# SwitchEthernet_-_Rev_A6.net
KiCad netlist of a schematic drawn in EAGLE
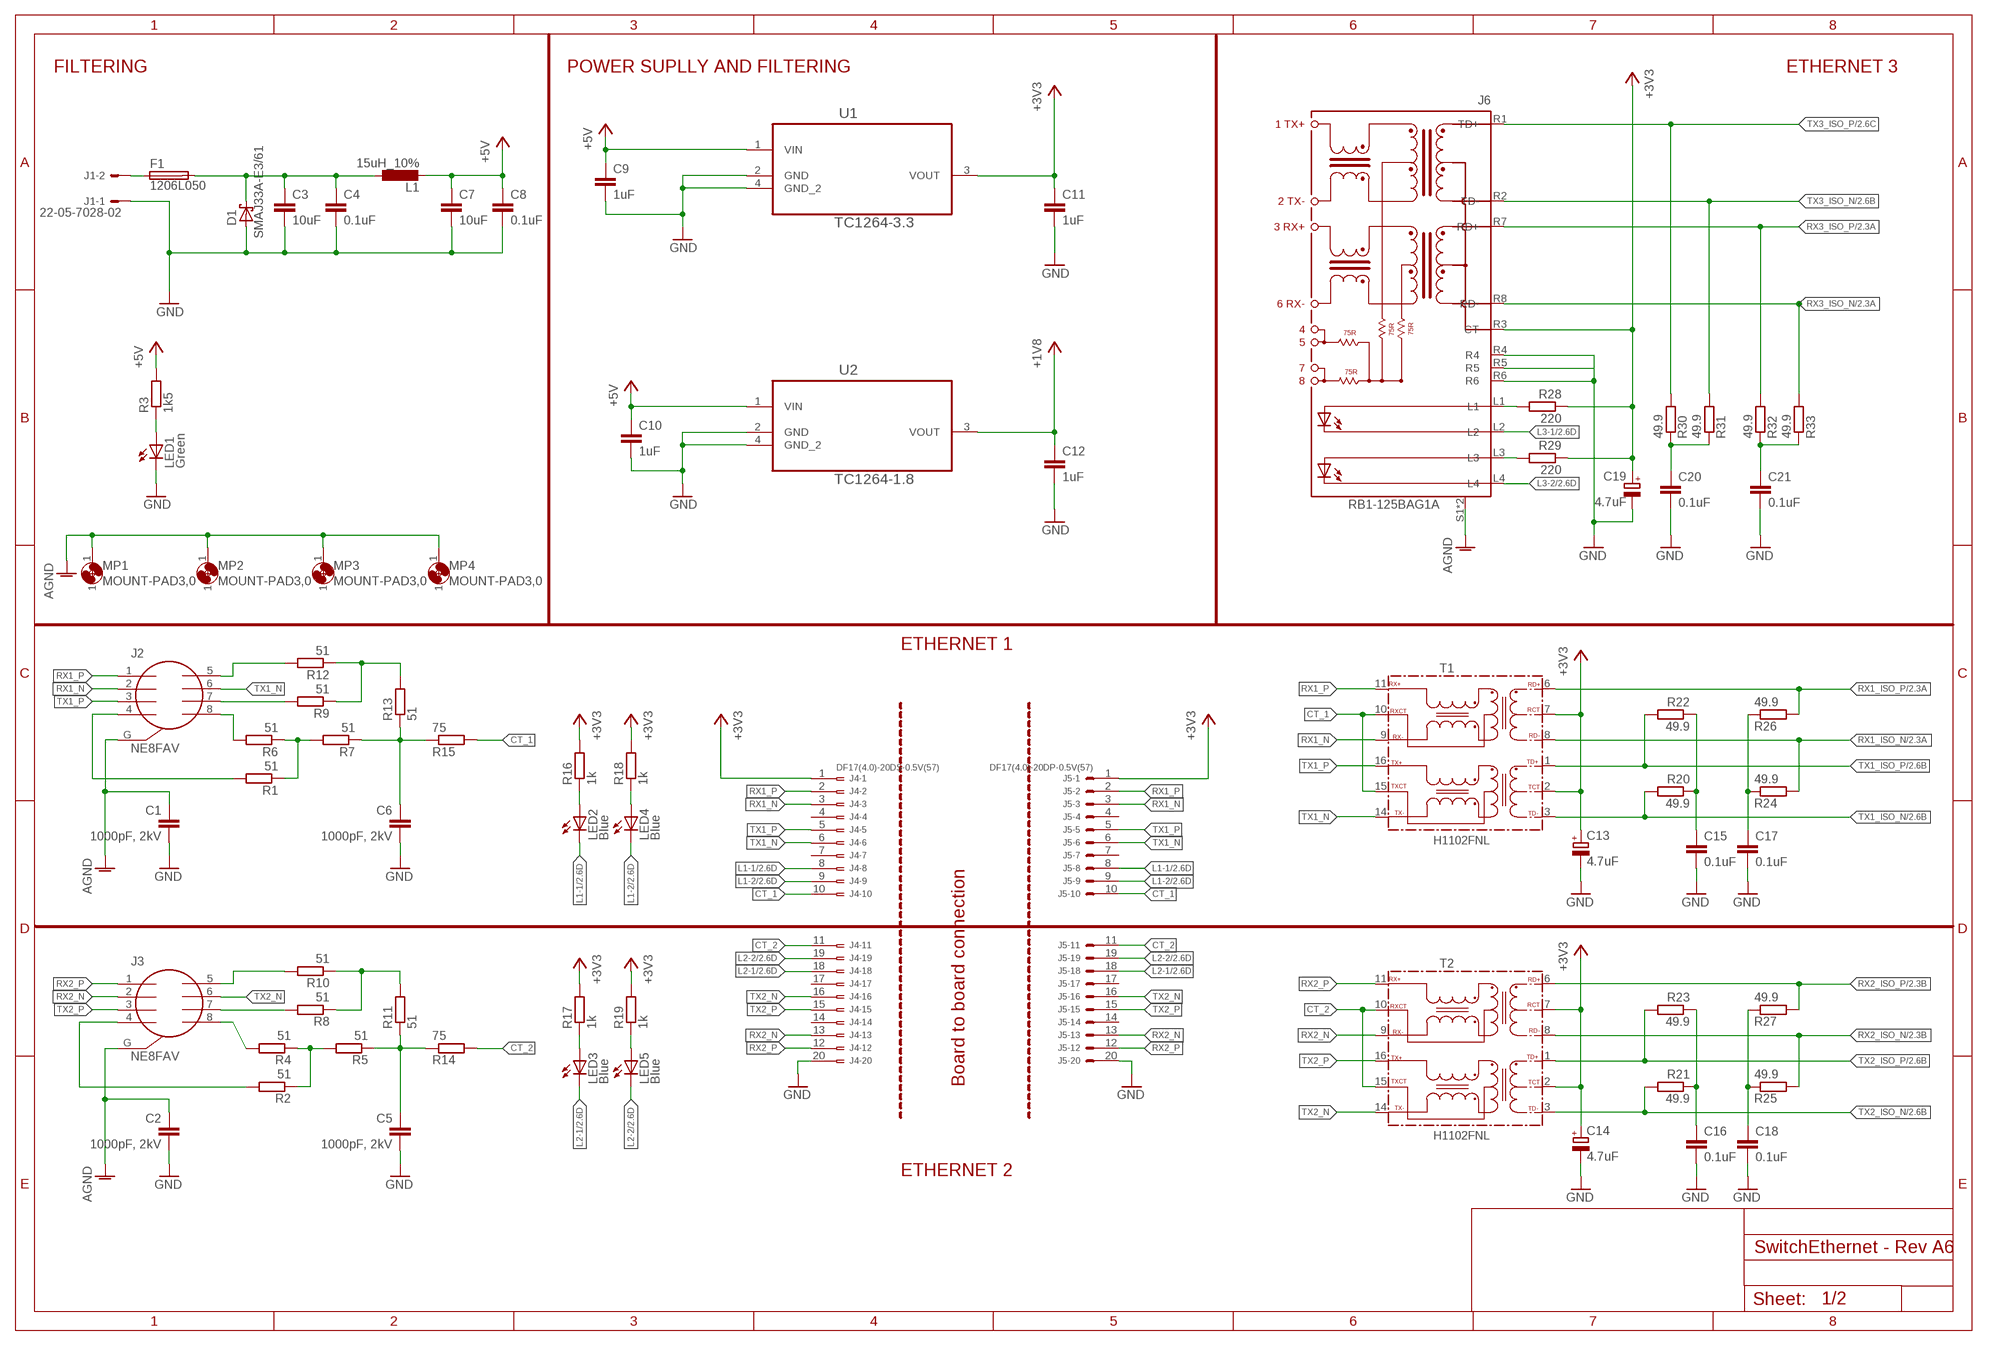
[diagram p0: schematic, sheet 1]
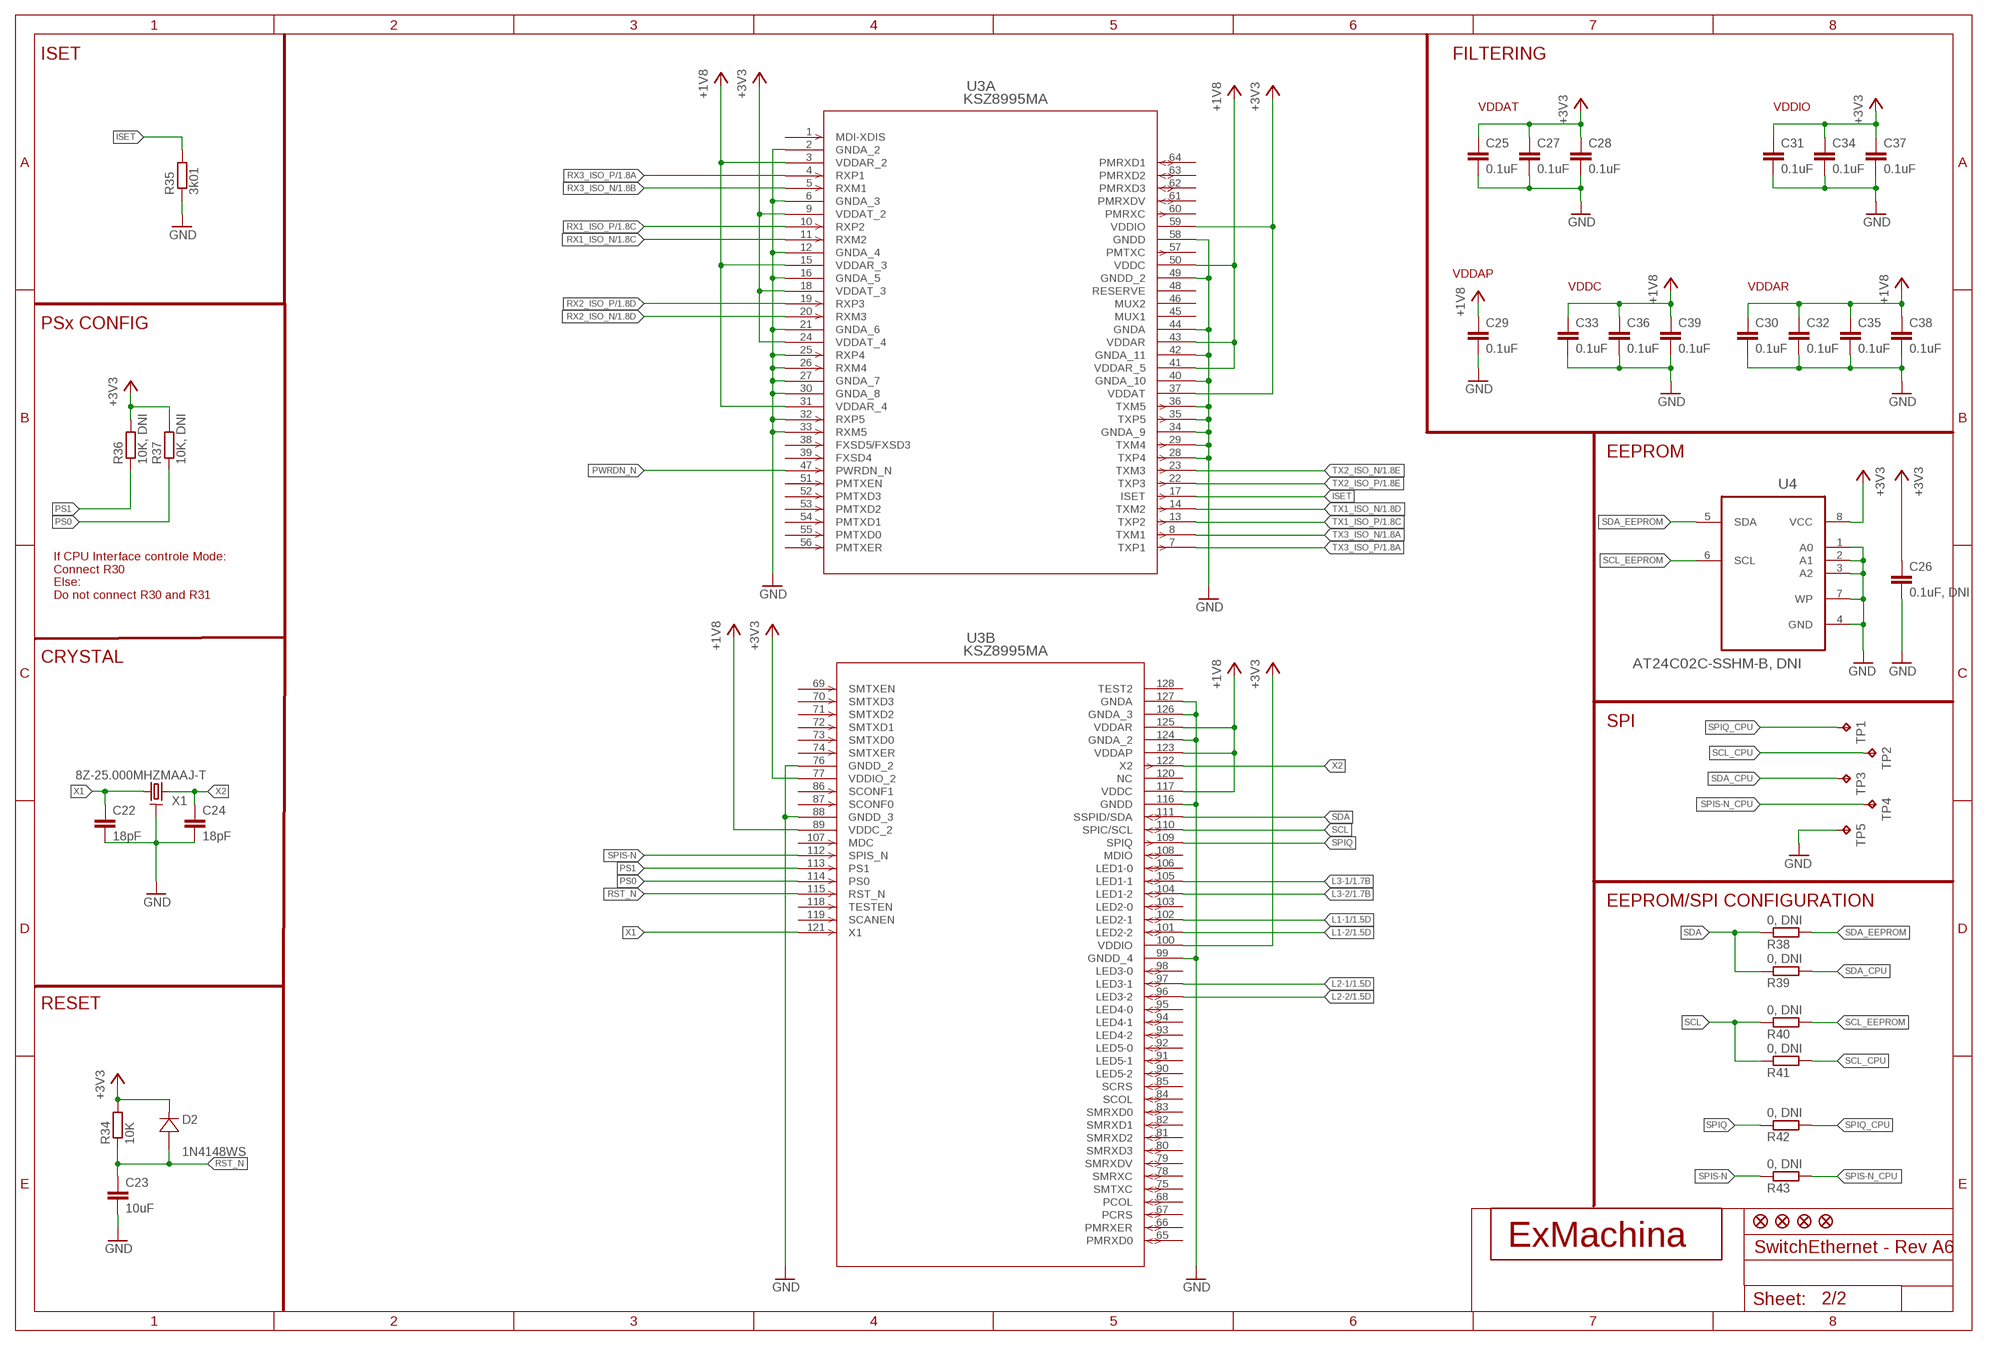
[diagram p1: schematic, sheet 2]

(export (version "E")
  (design (tool "Eeschema 10.0.6"))
  (components
    (comp (ref "C22")
      (value "18pF")
      (footprint "eagle-import:C0603")
      (fields (field (name "MF") "MURATA") (field (name "MPN") "GRM1885C1H180JA01D"))
      (libsource (lib "eagle-import") (part "C-EUC0603"))
    )
    (comp (ref "C23")
      (value "10uF")
      (footprint "eagle-import:C0603")
      (fields (field (name "MF") "MURATA") (field (name "MPN") "GRM32DR71C106KA01L"))
      (libsource (lib "eagle-import") (part "C-EUC0603"))
    )
    (comp (ref "C24")
      (value "18pF")
      (footprint "eagle-import:C0603")
      (fields (field (name "MF") "MURATA") (field (name "MPN") "GRM1885C1H180JA01D"))
      (libsource (lib "eagle-import") (part "C-EUC0603"))
    )
    (comp (ref "C25")
      (value "0.1uF")
      (footprint "eagle-import:C0603")
      (fields (field (name "MF") "MURATA") (field (name "MPN") "GRM188R71H104KA93D"))
      (libsource (lib "eagle-import") (part "C-EUC0603"))
    )
    (comp (ref "C26")
      (value "0.1uF, DNI")
      (footprint "eagle-import:C0603")
      (fields (field (name "MF") "MURATA") (field (name "MPN") "GRM188R71H104KA93D"))
      (libsource (lib "eagle-import") (part "C-EUC0603"))
    )
    (comp (ref "C27")
      (value "0.1uF")
      (footprint "eagle-import:C0603")
      (fields (field (name "MF") "MURATA") (field (name "MPN") "GRM188R71H104KA93D"))
      (libsource (lib "eagle-import") (part "C-EUC0603"))
    )
    (comp (ref "C28")
      (value "0.1uF")
      (footprint "eagle-import:C0603")
      (fields (field (name "MF") "MURATA") (field (name "MPN") "GRM188R71H104KA93D"))
      (libsource (lib "eagle-import") (part "C-EUC0603"))
    )
    (comp (ref "C29")
      (value "0.1uF")
      (footprint "eagle-import:C0603")
      (fields (field (name "MF") "MURATA") (field (name "MPN") "GRM188R71H104KA93D"))
      (libsource (lib "eagle-import") (part "C-EUC0603"))
    )
    (comp (ref "C30")
      (value "0.1uF")
      (footprint "eagle-import:C0603")
      (fields (field (name "MF") "MURATA") (field (name "MPN") "GRM188R71H104KA93D"))
      (libsource (lib "eagle-import") (part "C-EUC0603"))
    )
    (comp (ref "C31")
      (value "0.1uF")
      (footprint "eagle-import:C0603")
      (fields (field (name "MF") "MURATA") (field (name "MPN") "GRM188R71H104KA93D"))
      (libsource (lib "eagle-import") (part "C-EUC0603"))
    )
    (comp (ref "C32")
      (value "0.1uF")
      (footprint "eagle-import:C0603")
      (fields (field (name "MF") "MURATA") (field (name "MPN") "GRM188R71H104KA93D"))
      (libsource (lib "eagle-import") (part "C-EUC0603"))
    )
    (comp (ref "C33")
      (value "0.1uF")
      (footprint "eagle-import:C0603")
      (fields (field (name "MF") "MURATA") (field (name "MPN") "GRM188R71H104KA93D"))
      (libsource (lib "eagle-import") (part "C-EUC0603"))
    )
    (comp (ref "C34")
      (value "0.1uF")
      (footprint "eagle-import:C0603")
      (fields (field (name "MF") "MURATA") (field (name "MPN") "GRM188R71H104KA93D"))
      (libsource (lib "eagle-import") (part "C-EUC0603"))
    )
    (comp (ref "C35")
      (value "0.1uF")
      (footprint "eagle-import:C0603")
      (fields (field (name "MF") "MURATA") (field (name "MPN") "GRM188R71H104KA93D"))
      (libsource (lib "eagle-import") (part "C-EUC0603"))
    )
    (comp (ref "C36")
      (value "0.1uF")
      (footprint "eagle-import:C0603")
      (fields (field (name "MF") "MURATA") (field (name "MPN") "GRM188R71H104KA93D"))
      (libsource (lib "eagle-import") (part "C-EUC0603"))
    )
    (comp (ref "C37")
      (value "0.1uF")
      (footprint "eagle-import:C0603")
      (fields (field (name "MF") "MURATA") (field (name "MPN") "GRM188R71H104KA93D"))
      (libsource (lib "eagle-import") (part "C-EUC0603"))
    )
    (comp (ref "C38")
      (value "0.1uF")
      (footprint "eagle-import:C0603")
      (fields (field (name "MF") "MURATA") (field (name "MPN") "GRM188R71H104KA93D"))
      (libsource (lib "eagle-import") (part "C-EUC0603"))
    )
    (comp (ref "C39")
      (value "0.1uF")
      (footprint "eagle-import:C0603")
      (fields (field (name "MF") "MURATA") (field (name "MPN") "GRM188R71H104KA93D"))
      (libsource (lib "eagle-import") (part "C-EUC0603"))
    )
    (comp (ref "D2")
      (value "1N4148WS")
      (footprint "eagle-import:SOD323-W")
      (fields (field (name "MF") "ON SEMICONDUCTOR"))
      (libsource (lib "eagle-import") (part "1N4148WS"))
    )
    (comp (ref "JP1")
      (value "FIDUCIAL1X2")
      (footprint "eagle-import:FIDUCIAL-1X2")
      (libsource (lib "eagle-import") (part "FIDUCIAL1X2"))
    )
    (comp (ref "JP2")
      (value "FIDUCIAL1X2")
      (footprint "eagle-import:FIDUCIAL-1X2")
      (libsource (lib "eagle-import") (part "FIDUCIAL1X2"))
    )
    (comp (ref "JP3")
      (value "FIDUCIAL1X2")
      (footprint "eagle-import:FIDUCIAL-1X2")
      (libsource (lib "eagle-import") (part "FIDUCIAL1X2"))
    )
    (comp (ref "JP4")
      (value "FIDUCIAL1X2")
      (footprint "eagle-import:FIDUCIAL-1X2")
      (libsource (lib "eagle-import") (part "FIDUCIAL1X2"))
    )
    (comp (ref "R34")
      (value "10K")
      (footprint "eagle-import:R0603")
      (fields (field (name "MF") "YAGEO") (field (name "MPN") "RC0603FR-0710KL"))
      (libsource (lib "eagle-import") (part "R-EU_R0603"))
    )
    (comp (ref "R35")
      (value "3k01")
      (footprint "eagle-import:R0603")
      (fields (field (name "MF") "MULTICOMP") (field (name "MPN") "MCMR06X3001FTL"))
      (libsource (lib "eagle-import") (part "R-EU_R0603"))
    )
    (comp (ref "R36")
      (value "10K, DNI")
      (footprint "eagle-import:R0603")
      (fields (field (name "MF") "YAGEO") (field (name "MPN") "RC0603FR-0710KL"))
      (libsource (lib "eagle-import") (part "R-EU_R0603"))
    )
    (comp (ref "R37")
      (value "10K, DNI")
      (footprint "eagle-import:R0603")
      (fields (field (name "MF") "YAGEO") (field (name "MPN") "RC0603FR-0710KL"))
      (libsource (lib "eagle-import") (part "R-EU_R0603"))
    )
    (comp (ref "R38")
      (value "0, DNI")
      (footprint "eagle-import:R0603")
      (fields (field (name "MF") "YAGEO") (field (name "MPN") "RC0603FR-070RL"))
      (libsource (lib "eagle-import") (part "R-EU_R0603"))
    )
    (comp (ref "R39")
      (value "0, DNI")
      (footprint "eagle-import:R0603")
      (fields (field (name "MF") "YAGEO") (field (name "MPN") "RC0603FR-070RL"))
      (libsource (lib "eagle-import") (part "R-EU_R0603"))
    )
    (comp (ref "R40")
      (value "0, DNI")
      (footprint "eagle-import:R0603")
      (fields (field (name "MF") "YAGEO") (field (name "MPN") "RC0603FR-070RL"))
      (libsource (lib "eagle-import") (part "R-EU_R0603"))
    )
    (comp (ref "R41")
      (value "0, DNI")
      (footprint "eagle-import:R0603")
      (fields (field (name "MF") "YAGEO") (field (name "MPN") "RC0603FR-070RL"))
      (libsource (lib "eagle-import") (part "R-EU_R0603"))
    )
    (comp (ref "R42")
      (value "0, DNI")
      (footprint "eagle-import:R0603")
      (fields (field (name "MF") "YAGEO") (field (name "MPN") "RC0603FR-070RL"))
      (libsource (lib "eagle-import") (part "R-EU_R0603"))
    )
    (comp (ref "R43")
      (value "0, DNI")
      (footprint "eagle-import:R0603")
      (fields (field (name "MF") "YAGEO") (field (name "MPN") "RC0603FR-070RL"))
      (libsource (lib "eagle-import") (part "R-EU_R0603"))
    )
    (comp (ref "T3")
      (value "EXMACHINA-LOGO-NAME")
      (footprint "eagle-import:EXM-LOGO-BASELINE")
      (libsource (lib "eagle-import") (part "EXMACHINA-LOGO-NAME"))
    )
    (comp (ref "TP1")
      (value "TPB1,27")
      (footprint "eagle-import:B1,27")
      (libsource (lib "eagle-import") (part "TPB1,27"))
    )
    (comp (ref "TP2")
      (value "TPB1,27")
      (footprint "eagle-import:B1,27")
      (libsource (lib "eagle-import") (part "TPB1,27"))
    )
    (comp (ref "TP3")
      (value "TPB1,27")
      (footprint "eagle-import:B1,27")
      (libsource (lib "eagle-import") (part "TPB1,27"))
    )
    (comp (ref "TP4")
      (value "TPB1,27")
      (footprint "eagle-import:B1,27")
      (libsource (lib "eagle-import") (part "TPB1,27"))
    )
    (comp (ref "TP5")
      (value "TPB1,27")
      (footprint "eagle-import:B1,27")
      (libsource (lib "eagle-import") (part "TPB1,27"))
    )
    (comp (ref "U3")
      (value "KSZ8995MA")
      (footprint "eagle-import:PQFP-128_MQL")
      (fields
        (field (name "MF") "MICROCHIP")
        (field (name "MPN") "KSZ8995MA")
        (field (name "OC_FARNELL") "2509844")
        (field (name "OC_NEWARK") "unknown")
      )
      (libsource (lib "eagle-import") (part "KSZ8995MA"))
    )
    (comp (ref "U4")
      (value "AT24C02C-SSHM-B, DNI")
      (footprint "eagle-import:SOIC127P600X175-8N")
      (fields
        (field (name "MPN") "AT24C02C-SSHM-B")
        (field (name "MF") "MICROCHIP")
        (field (name "OC_FARNELL") "1971995")
      )
      (libsource (lib "eagle-import") (part "AT24C02C-SSHM-B"))
    )
    (comp (ref "X1")
      (value "8Z-25.000MHZMAAJ-T")
      (footprint "eagle-import:SMD2.5X2")
      (fields (field (name "MF") "TXC") (field (name "MPN") "8Z-25.000MAAJ-T"))
      (libsource (lib "eagle-import") (part "8Z-25.000MHZMAAJ-T"))
    )
    (comp (ref "C1")
      (value "1000pF, 2kV")
      (footprint "eagle-import:C1206")
      (fields (field (name "MF") "MULTICOMP") (field (name "MPN") "MC1206B102K202CT"))
      (libsource (lib "eagle-import") (part "C-EUC1206"))
    )
    (comp (ref "C2")
      (value "1000pF, 2kV")
      (footprint "eagle-import:C1206")
      (fields (field (name "MF") "MULTICOMP") (field (name "MPN") "MC1206B102K202CT"))
      (libsource (lib "eagle-import") (part "C-EUC1206"))
    )
    (comp (ref "C3")
      (value "10uF")
      (footprint "eagle-import:C0603")
      (fields (field (name "MF") "MURATA") (field (name "MPN") "GRM32DR71C106KA01L"))
      (libsource (lib "eagle-import") (part "C-EUC0603"))
    )
    (comp (ref "C4")
      (value "0.1uF")
      (footprint "eagle-import:C0603")
      (fields (field (name "MF") "MURATA") (field (name "MPN") "GRM188R71H104KA93D"))
      (libsource (lib "eagle-import") (part "C-EUC0603"))
    )
    (comp (ref "C5")
      (value "1000pF, 2kV")
      (footprint "eagle-import:C1206")
      (fields (field (name "MF") "MULTICOMP") (field (name "MPN") "MC1206B102K202CT"))
      (libsource (lib "eagle-import") (part "C-EUC1206"))
    )
    (comp (ref "C6")
      (value "1000pF, 2kV")
      (footprint "eagle-import:C1206")
      (fields (field (name "MF") "MULTICOMP") (field (name "MPN") "MC1206B102K202CT"))
      (libsource (lib "eagle-import") (part "C-EUC1206"))
    )
    (comp (ref "C7")
      (value "10uF")
      (footprint "eagle-import:C0603")
      (fields (field (name "MF") "MURATA") (field (name "MPN") "GRM32DR71C106KA01L"))
      (libsource (lib "eagle-import") (part "C-EUC0603"))
    )
    (comp (ref "C8")
      (value "0.1uF")
      (footprint "eagle-import:C0603")
      (fields (field (name "MF") "MURATA") (field (name "MPN") "GRM188R71H104KA93D"))
      (libsource (lib "eagle-import") (part "C-EUC0603"))
    )
    (comp (ref "C9")
      (value "1uF")
      (footprint "eagle-import:C0603")
      (fields (field (name "MF") "MURATA") (field (name "MPN") "GRM188R61C105KA93D"))
      (libsource (lib "eagle-import") (part "C-EUC0603"))
    )
    (comp (ref "C10")
      (value "1uF")
      (footprint "eagle-import:C0603")
      (fields (field (name "MF") "MURATA") (field (name "MPN") "GRM188R61C105KA93D"))
      (libsource (lib "eagle-import") (part "C-EUC0603"))
    )
    (comp (ref "C11")
      (value "1uF")
      (footprint "eagle-import:C0603")
      (fields (field (name "MF") "MURATA") (field (name "MPN") "GRM188R61C105KA93D"))
      (libsource (lib "eagle-import") (part "C-EUC0603"))
    )
    (comp (ref "C12")
      (value "1uF")
      (footprint "eagle-import:C0603")
      (fields (field (name "MF") "MURATA") (field (name "MPN") "GRM188R61C105KA93D"))
      (libsource (lib "eagle-import") (part "C-EUC0603"))
    )
    (comp (ref "C13")
      (value "4.7uF")
      (footprint "eagle-import:CT3216")
      (fields (field (name "MF") "KEMET") (field (name "MPN") "T491A475K016AT"))
      (libsource (lib "eagle-import") (part "CPOL-EUCT3216"))
    )
    (comp (ref "C14")
      (value "4.7uF")
      (footprint "eagle-import:CT3216")
      (fields (field (name "MF") "KEMET") (field (name "MPN") "T491A475K016AT"))
      (libsource (lib "eagle-import") (part "CPOL-EUCT3216"))
    )
    (comp (ref "C15")
      (value "0.1uF")
      (footprint "eagle-import:C0603")
      (fields (field (name "MF") "MURATA") (field (name "MPN") "GRM188R71H104KA93D"))
      (libsource (lib "eagle-import") (part "C-EUC0603"))
    )
    (comp (ref "C16")
      (value "0.1uF")
      (footprint "eagle-import:C0603")
      (fields (field (name "MF") "MURATA") (field (name "MPN") "GRM188R71H104KA93D"))
      (libsource (lib "eagle-import") (part "C-EUC0603"))
    )
    (comp (ref "C17")
      (value "0.1uF")
      (footprint "eagle-import:C0603")
      (fields (field (name "MF") "MURATA") (field (name "MPN") "GRM188R71H104KA93D"))
      (libsource (lib "eagle-import") (part "C-EUC0603"))
    )
    (comp (ref "C18")
      (value "0.1uF")
      (footprint "eagle-import:C0603")
      (fields (field (name "MF") "MURATA") (field (name "MPN") "GRM188R71H104KA93D"))
      (libsource (lib "eagle-import") (part "C-EUC0603"))
    )
    (comp (ref "C19")
      (value "4.7uF")
      (footprint "eagle-import:CT3216")
      (fields (field (name "MF") "KEMET") (field (name "MPN") "T491A475K016AT"))
      (libsource (lib "eagle-import") (part "CPOL-EUCT3216"))
    )
    (comp (ref "C20")
      (value "0.1uF")
      (footprint "eagle-import:C0603")
      (fields (field (name "MF") "MURATA") (field (name "MPN") "GRM188R71H104KA93D"))
      (libsource (lib "eagle-import") (part "C-EUC0603"))
    )
    (comp (ref "C21")
      (value "0.1uF")
      (footprint "eagle-import:C0603")
      (fields (field (name "MF") "MURATA") (field (name "MPN") "GRM188R71H104KA93D"))
      (libsource (lib "eagle-import") (part "C-EUC0603"))
    )
    (comp (ref "D1")
      (value "SMAJ33A-E3/61")
      (footprint "eagle-import:DIODE_DO-214AC")
      (fields (field (name "MF") "VISHAY"))
      (libsource (lib "eagle-import") (part "SMAJ33A-E3/61"))
    )
    (comp (ref "F1")
      (value "1206L050")
      (footprint "eagle-import:1206L")
      (fields (field (name "MF") "LITTELFUSE") (field (name "MPN") "1206L050YR"))
      (libsource (lib "eagle-import") (part "1206L050"))
    )
    (comp (ref "J1")
      (value "22-05-7028-02")
      (footprint "eagle-import:7395-02")
      (fields (field (name "MF") "MOLEX") (field (name "MPN") "22-05-7028"))
      (libsource (lib "eagle-import") (part "22-?-0205-7028"))
    )
    (comp (ref "J2")
      (value "NE8FAV")
      (footprint "eagle-import:NE8FAV")
      (fields (field (name "MF") "NEUTRIK") (field (name "OC_FARNELL") "1202031"))
      (libsource (lib "eagle-import") (part "NE8FAV"))
    )
    (comp (ref "J3")
      (value "NE8FAV")
      (footprint "eagle-import:NE8FAV")
      (fields (field (name "MF") "NEUTRIK") (field (name "OC_FARNELL") "1202031"))
      (libsource (lib "eagle-import") (part "NE8FAV"))
    )
    (comp (ref "J4")
      (value "DF17(4.0)-20DS-0.5V(57)")
      (footprint "eagle-import:DF17-20DS")
      (fields
        (field (name "MF") "HIROSE(HRS)")
        (field (name "MPN") "DF17(4.0)-20DS-0.5V(57)")
        (field (name "OC_FARNELL") "2300346")
        (field (name "OC_NEWARK") "unknown")
      )
      (libsource (lib "eagle-import") (part "DF17(?)-20DS-0.5V(57)4.0"))
    )
    (comp (ref "J5")
      (value "DF17(4.0)-20DP-0.5V(57)")
      (footprint "eagle-import:DF17-20DP")
      (fields
        (field (name "MF") "HIROSE(HRS)")
        (field (name "MPN") "DF17(4.0)-20DP-0.5V(57)")
        (field (name "OC_FARNELL") "2300344")
        (field (name "OC_NEWARK") "unknown")
      )
      (libsource (lib "eagle-import") (part "DF17(?)-20DP-0.5V(57)4.0"))
    )
    (comp (ref "J6")
      (value "RB1-125BAG1A")
      (footprint "eagle-import:WIZNET_RB1-125BAG1A")
      (libsource (lib "eagle-import") (part "RB1-125BAG1A"))
    )
    (comp (ref "L1")
      (value "15uH_10%")
      (footprint "eagle-import:L4532M")
      (fields (field (name "MF") "MURATA") (field (name "MPN") "LQH43CN150K03L"))
      (libsource (lib "eagle-import") (part "L-EUL4532C"))
    )
    (comp (ref "LED1")
      (value "Green")
      (footprint "eagle-import:CHIP-LED0603")
      (fields (field (name "MF") "MULTICOMP") (field (name "MPN") "OVS-0604"))
      (libsource (lib "eagle-import") (part "LEDCHIP-LED0603"))
    )
    (comp (ref "LED2")
      (value "Blue")
      (footprint "eagle-import:CHIP-LED0603")
      (fields (field (name "MF") "MULTICOMP") (field (name "MPN") "OVS-0603"))
      (libsource (lib "eagle-import") (part "LEDCHIP-LED0603"))
    )
    (comp (ref "LED3")
      (value "Blue")
      (footprint "eagle-import:CHIP-LED0603")
      (fields (field (name "MF") "MULTICOMP") (field (name "MPN") "OVS-0603"))
      (libsource (lib "eagle-import") (part "LEDCHIP-LED0603"))
    )
    (comp (ref "LED4")
      (value "Blue")
      (footprint "eagle-import:CHIP-LED0603")
      (fields (field (name "MF") "MULTICOMP") (field (name "MPN") "OVS-0603"))
      (libsource (lib "eagle-import") (part "LEDCHIP-LED0603"))
    )
    (comp (ref "LED5")
      (value "Blue")
      (footprint "eagle-import:CHIP-LED0603")
      (fields (field (name "MF") "MULTICOMP") (field (name "MPN") "OVS-0603"))
      (libsource (lib "eagle-import") (part "LEDCHIP-LED0603"))
    )
    (comp (ref "MP1")
      (value "MOUNT-PAD3,0")
      (footprint "eagle-import:P3,0")
      (libsource (lib "eagle-import") (part "MOUNT-PAD3,0"))
    )
    (comp (ref "MP2")
      (value "MOUNT-PAD3,0")
      (footprint "eagle-import:P3,0")
      (libsource (lib "eagle-import") (part "MOUNT-PAD3,0"))
    )
    (comp (ref "MP3")
      (value "MOUNT-PAD3,0")
      (footprint "eagle-import:P3,0")
      (libsource (lib "eagle-import") (part "MOUNT-PAD3,0"))
    )
    (comp (ref "MP4")
      (value "MOUNT-PAD3,0")
      (footprint "eagle-import:P3,0")
      (libsource (lib "eagle-import") (part "MOUNT-PAD3,0"))
    )
    (comp (ref "R1")
      (value "51")
      (footprint "eagle-import:R0603")
      (fields (field (name "MF") "YAGEO") (field (name "MPN") "RC0603FR-0751RL"))
      (libsource (lib "eagle-import") (part "R-EU_R0603"))
    )
    (comp (ref "R2")
      (value "51")
      (footprint "eagle-import:R0603")
      (fields (field (name "MF") "YAGEO") (field (name "MPN") "RC0603FR-0751RL"))
      (libsource (lib "eagle-import") (part "R-EU_R0603"))
    )
    (comp (ref "R3")
      (value "1k5")
      (footprint "eagle-import:R0603")
      (fields (field (name "MF") "YAGEO") (field (name "MPN") "RC0603FR-071K5L"))
      (libsource (lib "eagle-import") (part "R-EU_R0603"))
    )
    (comp (ref "R4")
      (value "51")
      (footprint "eagle-import:R0603")
      (fields (field (name "MF") "YAGEO") (field (name "MPN") "RC0603FR-0751RL"))
      (libsource (lib "eagle-import") (part "R-EU_R0603"))
    )
    (comp (ref "R5")
      (value "51")
      (footprint "eagle-import:R0603")
      (fields (field (name "MF") "YAGEO") (field (name "MPN") "RC0603FR-0751RL"))
      (libsource (lib "eagle-import") (part "R-EU_R0603"))
    )
    (comp (ref "R6")
      (value "51")
      (footprint "eagle-import:R0603")
      (fields (field (name "MF") "YAGEO") (field (name "MPN") "RC0603FR-0751RL"))
      (libsource (lib "eagle-import") (part "R-EU_R0603"))
    )
    (comp (ref "R7")
      (value "51")
      (footprint "eagle-import:R0603")
      (fields (field (name "MF") "YAGEO") (field (name "MPN") "RC0603FR-0751RL"))
      (libsource (lib "eagle-import") (part "R-EU_R0603"))
    )
    (comp (ref "R8")
      (value "51")
      (footprint "eagle-import:R0603")
      (fields (field (name "MF") "YAGEO") (field (name "MPN") "RC0603FR-0751RL"))
      (libsource (lib "eagle-import") (part "R-EU_R0603"))
    )
    (comp (ref "R9")
      (value "51")
      (footprint "eagle-import:R0603")
      (fields (field (name "MF") "YAGEO") (field (name "MPN") "RC0603FR-0751RL"))
      (libsource (lib "eagle-import") (part "R-EU_R0603"))
    )
    (comp (ref "R10")
      (value "51")
      (footprint "eagle-import:R0603")
      (fields (field (name "MF") "YAGEO") (field (name "MPN") "RC0603FR-0751RL"))
      (libsource (lib "eagle-import") (part "R-EU_R0603"))
    )
    (comp (ref "R11")
      (value "51")
      (footprint "eagle-import:R0603")
      (fields (field (name "MF") "YAGEO") (field (name "MPN") "RC0603FR-0751RL"))
      (libsource (lib "eagle-import") (part "R-EU_R0603"))
    )
    (comp (ref "R12")
      (value "51")
      (footprint "eagle-import:R0603")
      (fields (field (name "MF") "YAGEO") (field (name "MPN") "RC0603FR-0751RL"))
      (libsource (lib "eagle-import") (part "R-EU_R0603"))
    )
    (comp (ref "R13")
      (value "51")
      (footprint "eagle-import:R0603")
      (fields (field (name "MF") "YAGEO") (field (name "MPN") "RC0603FR-0751RL"))
      (libsource (lib "eagle-import") (part "R-EU_R0603"))
    )
    (comp (ref "R14")
      (value "75")
      (footprint "eagle-import:R0603")
      (fields (field (name "MF") "YAGEO") (field (name "MPN") "RC0603FR-0775RL"))
      (libsource (lib "eagle-import") (part "R-EU_R0603"))
    )
    (comp (ref "R15")
      (value "75")
      (footprint "eagle-import:R0603")
      (fields (field (name "MF") "YAGEO") (field (name "MPN") "RC0603FR-0775RL"))
      (libsource (lib "eagle-import") (part "R-EU_R0603"))
    )
    (comp (ref "R16")
      (value "1k")
      (footprint "eagle-import:R0603")
      (fields (field (name "MF") "YAGEO") (field (name "MPN") "RC0603FR-071KL."))
      (libsource (lib "eagle-import") (part "R-EU_R0603"))
    )
    (comp (ref "R17")
      (value "1k")
      (footprint "eagle-import:R0603")
      (fields (field (name "MF") "YAGEO") (field (name "MPN") "RC0603FR-071KL."))
      (libsource (lib "eagle-import") (part "R-EU_R0603"))
    )
    (comp (ref "R18")
      (value "1k")
      (footprint "eagle-import:R0603")
      (fields (field (name "MF") "YAGEO") (field (name "MPN") "RC0603FR-071KL."))
      (libsource (lib "eagle-import") (part "R-EU_R0603"))
    )
    (comp (ref "R19")
      (value "1k")
      (footprint "eagle-import:R0603")
      (fields (field (name "MF") "YAGEO") (field (name "MPN") "RC0603FR-071KL."))
      (libsource (lib "eagle-import") (part "R-EU_R0603"))
    )
    (comp (ref "R20")
      (value "49.9")
      (footprint "eagle-import:R0603")
      (fields (field (name "MF") "MULTICOMP") (field (name "MPN") "MCWR06X49R9FTL"))
      (libsource (lib "eagle-import") (part "R-EU_R0603"))
    )
    (comp (ref "R21")
      (value "49.9")
      (footprint "eagle-import:R0603")
      (fields (field (name "MF") "MULTICOMP") (field (name "MPN") "MCWR06X49R9FTL"))
      (libsource (lib "eagle-import") (part "R-EU_R0603"))
    )
    (comp (ref "R22")
      (value "49.9")
      (footprint "eagle-import:R0603")
      (fields (field (name "MF") "MULTICOMP") (field (name "MPN") "MCWR06X49R9FTL"))
      (libsource (lib "eagle-import") (part "R-EU_R0603"))
    )
    (comp (ref "R23")
      (value "49.9")
      (footprint "eagle-import:R0603")
      (fields (field (name "MF") "MULTICOMP") (field (name "MPN") "MCWR06X49R9FTL"))
      (libsource (lib "eagle-import") (part "R-EU_R0603"))
    )
    (comp (ref "R24")
      (value "49.9")
      (footprint "eagle-import:R0603")
      (fields (field (name "MF") "MULTICOMP") (field (name "MPN") "MCWR06X49R9FTL"))
      (libsource (lib "eagle-import") (part "R-EU_R0603"))
    )
    (comp (ref "R25")
      (value "49.9")
      (footprint "eagle-import:R0603")
      (fields (field (name "MF") "MULTICOMP") (field (name "MPN") "MCWR06X49R9FTL"))
      (libsource (lib "eagle-import") (part "R-EU_R0603"))
    )
    (comp (ref "R26")
      (value "49.9")
      (footprint "eagle-import:R0603")
      (fields (field (name "MF") "MULTICOMP") (field (name "MPN") "MCWR06X49R9FTL"))
      (libsource (lib "eagle-import") (part "R-EU_R0603"))
    )
    (comp (ref "R27")
      (value "49.9")
      (footprint "eagle-import:R0603")
      (fields (field (name "MF") "MULTICOMP") (field (name "MPN") "MCWR06X49R9FTL"))
      (libsource (lib "eagle-import") (part "R-EU_R0603"))
    )
    (comp (ref "R28")
      (value "220")
      (footprint "eagle-import:R0603")
      (fields (field (name "MF") "YAGEO (PHYCOMP)") (field (name "MPN") "RC0603FR-07220RL"))
      (libsource (lib "eagle-import") (part "R-EU_R0603"))
    )
    (comp (ref "R29")
      (value "220")
      (footprint "eagle-import:R0603")
      (fields (field (name "MF") "YAGEO (PHYCOMP)") (field (name "MPN") "RC0603FR-07220RL"))
      (libsource (lib "eagle-import") (part "R-EU_R0603"))
    )
    (comp (ref "R30")
      (value "49.9")
      (footprint "eagle-import:R0603")
      (fields (field (name "MF") "MULTICOMP") (field (name "MPN") "MCWR06X49R9FTL"))
      (libsource (lib "eagle-import") (part "R-EU_R0603"))
    )
    (comp (ref "R31")
      (value "49.9")
      (footprint "eagle-import:R0603")
      (fields (field (name "MF") "MULTICOMP") (field (name "MPN") "MCWR06X49R9FTL"))
      (libsource (lib "eagle-import") (part "R-EU_R0603"))
    )
    (comp (ref "R32")
      (value "49.9")
      (footprint "eagle-import:R0603")
      (fields (field (name "MF") "MULTICOMP") (field (name "MPN") "MCWR06X49R9FTL"))
      (libsource (lib "eagle-import") (part "R-EU_R0603"))
    )
    (comp (ref "R33")
      (value "49.9")
      (footprint "eagle-import:R0603")
      (fields (field (name "MF") "MULTICOMP") (field (name "MPN") "MCWR06X49R9FTL"))
      (libsource (lib "eagle-import") (part "R-EU_R0603"))
    )
    (comp (ref "T1")
      (value "H1102FNL")
      (footprint "eagle-import:HXXXX")
      (libsource (lib "eagle-import") (part "H1102FNL"))
    )
    (comp (ref "T2")
      (value "H1102FNL")
      (footprint "eagle-import:HXXXX")
      (libsource (lib "eagle-import") (part "H1102FNL"))
    )
    (comp (ref "U1")
      (value "TC1264-3.3")
      (footprint "eagle-import:SOT230P700X180-4N")
      (libsource (lib "eagle-import") (part "TC1264-3.3"))
    )
    (comp (ref "U2")
      (value "TC1264-1.8")
      (footprint "eagle-import:SOT230P700X180-4N")
      (libsource (lib "eagle-import") (part "TC1264-1.8"))
    )
  )
  (nets
    (net (code "1") (name "+1V8") (class "Default")
      (node (ref "C12") (pin "1") (pinfunction "1_1") (pintype "passive"))
      (node (ref "C29") (pin "1") (pinfunction "1_1") (pintype "passive"))
      (node (ref "C30") (pin "1") (pinfunction "1_1") (pintype "passive"))
      (node (ref "C32") (pin "1") (pinfunction "1_1") (pintype "passive"))
      (node (ref "C33") (pin "1") (pinfunction "1_1") (pintype "passive"))
      (node (ref "C35") (pin "1") (pinfunction "1_1") (pintype "passive"))
      (node (ref "C36") (pin "1") (pinfunction "1_1") (pintype "passive"))
      (node (ref "C38") (pin "1") (pinfunction "1_1") (pintype "passive"))
      (node (ref "C39") (pin "1") (pinfunction "1_1") (pintype "passive"))
      (node (ref "U2") (pin "3") (pinfunction "VOUT_3") (pintype "output"))
      (node (ref "U3") (pin "117") (pinfunction "VDDC_117") (pintype "power_in"))
      (node (ref "U3") (pin "123") (pinfunction "VDDAP_123") (pintype "power_in"))
      (node (ref "U3") (pin "125") (pinfunction "VDDAR_125") (pintype "power_in"))
      (node (ref "U3") (pin "15") (pinfunction "VDDAR_3_15") (pintype "power_in"))
      (node (ref "U3") (pin "3") (pinfunction "VDDAR_2_3") (pintype "power_in"))
      (node (ref "U3") (pin "31") (pinfunction "VDDAR_4_31") (pintype "power_in"))
      (node (ref "U3") (pin "41") (pinfunction "VDDAR_5_41") (pintype "power_in"))
      (node (ref "U3") (pin "43") (pinfunction "VDDAR_43") (pintype "power_in"))
      (node (ref "U3") (pin "50") (pinfunction "VDDC_50") (pintype "power_in"))
      (node (ref "U3") (pin "89") (pinfunction "VDDC_2_89") (pintype "power_in"))
    )
    (net (code "2") (name "+3V3") (class "Default")
      (node (ref "C11") (pin "1") (pinfunction "1_1") (pintype "passive"))
      (node (ref "C13") (pin "+") (pinfunction "+_+") (pintype "passive"))
      (node (ref "C14") (pin "+") (pinfunction "+_+") (pintype "passive"))
      (node (ref "C19") (pin "+") (pinfunction "+_+") (pintype "passive"))
      (node (ref "C25") (pin "1") (pinfunction "1_1") (pintype "passive"))
      (node (ref "C26") (pin "1") (pinfunction "1_1") (pintype "passive"))
      (node (ref "C27") (pin "1") (pinfunction "1_1") (pintype "passive"))
      (node (ref "C28") (pin "1") (pinfunction "1_1") (pintype "passive"))
      (node (ref "C31") (pin "1") (pinfunction "1_1") (pintype "passive"))
      (node (ref "C34") (pin "1") (pinfunction "1_1") (pintype "passive"))
      (node (ref "C37") (pin "1") (pinfunction "1_1") (pintype "passive"))
      (node (ref "D2") (pin "C") (pinfunction "1_C") (pintype "passive"))
      (node (ref "J4") (pin "1") (pinfunction "P_1") (pintype "bidirectional"))
      (node (ref "J5") (pin "1") (pinfunction "P_1") (pintype "bidirectional"))
      (node (ref "J6") (pin "R3") (pinfunction "CT_R3") (pintype "input"))
      (node (ref "R16") (pin "2") (pinfunction "2_2") (pintype "passive"))
      (node (ref "R17") (pin "2") (pinfunction "2_2") (pintype "passive"))
      (node (ref "R18") (pin "2") (pinfunction "2_2") (pintype "passive"))
      (node (ref "R19") (pin "2") (pinfunction "2_2") (pintype "passive"))
      (node (ref "R28") (pin "1") (pinfunction "1_1") (pintype "passive"))
      (node (ref "R29") (pin "1") (pinfunction "1_1") (pintype "passive"))
      (node (ref "R34") (pin "2") (pinfunction "2_2") (pintype "passive"))
      (node (ref "R36") (pin "2") (pinfunction "2_2") (pintype "passive"))
      (node (ref "R37") (pin "2") (pinfunction "2_2") (pintype "passive"))
      (node (ref "T1") (pin "2") (pinfunction "TCT_2") (pintype "bidirectional"))
      (node (ref "T1") (pin "7") (pinfunction "RCT_7") (pintype "bidirectional"))
      (node (ref "T2") (pin "2") (pinfunction "TCT_2") (pintype "bidirectional"))
      (node (ref "T2") (pin "7") (pinfunction "RCT_7") (pintype "bidirectional"))
      (node (ref "U1") (pin "3") (pinfunction "VOUT_3") (pintype "output"))
      (node (ref "U3") (pin "100") (pinfunction "VDDIO_100") (pintype "power_in"))
      (node (ref "U3") (pin "18") (pinfunction "VDDAT_3_18") (pintype "power_in"))
      (node (ref "U3") (pin "24") (pinfunction "VDDAT_4_24") (pintype "power_in"))
      (node (ref "U3") (pin "37") (pinfunction "VDDAT_37") (pintype "power_in"))
      (node (ref "U3") (pin "59") (pinfunction "VDDIO_59") (pintype "power_in"))
      (node (ref "U3") (pin "77") (pinfunction "VDDIO_2_77") (pintype "power_in"))
      (node (ref "U3") (pin "9") (pinfunction "VDDAT_2_9") (pintype "power_in"))
      (node (ref "U4") (pin "8") (pinfunction "VCC_8") (pintype "power_in"))
    )
    (net (code "3") (name "+5V") (class "Default")
      (node (ref "C10") (pin "1") (pinfunction "1_1") (pintype "passive"))
      (node (ref "C7") (pin "1") (pinfunction "1_1") (pintype "passive"))
      (node (ref "C8") (pin "1") (pinfunction "1_1") (pintype "passive"))
      (node (ref "C9") (pin "1") (pinfunction "1_1") (pintype "passive"))
      (node (ref "L1") (pin "2") (pinfunction "2_2") (pintype "passive"))
      (node (ref "R3") (pin "2") (pinfunction "2_2") (pintype "passive"))
      (node (ref "U1") (pin "1") (pinfunction "VIN_1") (pintype "input"))
      (node (ref "U2") (pin "1") (pinfunction "VIN_1") (pintype "input"))
    )
    (net (code "4") (name "AGND") (class "Default")
      (node (ref "C1") (pin "1") (pinfunction "1_1") (pintype "passive"))
      (node (ref "C2") (pin "1") (pinfunction "1_1") (pintype "passive"))
      (node (ref "J2") (pin "G") (pinfunction "G_G") (pintype "passive"))
      (node (ref "J3") (pin "G") (pinfunction "G_G") (pintype "passive"))
      (node (ref "J6") (pin "S1") (pinfunction "P$1_S1") (pintype "bidirectional"))
      (node (ref "J6") (pin "S2") (pinfunction "P$1_S2") (pintype "bidirectional"))
      (node (ref "MP1") (pin "1") (pinfunction "1_1") (pintype "power_in"))
      (node (ref "MP2") (pin "1") (pinfunction "1_1") (pintype "power_in"))
      (node (ref "MP3") (pin "1") (pinfunction "1_1") (pintype "power_in"))
      (node (ref "MP4") (pin "1") (pinfunction "1_1") (pintype "power_in"))
    )
    (net (code "5") (name "CT_1") (class "Default")
      (node (ref "J4") (pin "10") (pinfunction "P_10") (pintype "bidirectional"))
      (node (ref "J5") (pin "10") (pinfunction "P_10") (pintype "bidirectional"))
      (node (ref "R15") (pin "2") (pinfunction "2_2") (pintype "passive"))
      (node (ref "T1") (pin "10") (pinfunction "RXCT_10") (pintype "bidirectional"))
      (node (ref "T1") (pin "15") (pinfunction "TXCT_15") (pintype "bidirectional"))
    )
    (net (code "6") (name "CT_2") (class "Default")
      (node (ref "J4") (pin "11") (pinfunction "P_11") (pintype "bidirectional"))
      (node (ref "J5") (pin "11") (pinfunction "P_11") (pintype "bidirectional"))
      (node (ref "R14") (pin "2") (pinfunction "2_2") (pintype "passive"))
      (node (ref "T2") (pin "10") (pinfunction "RXCT_10") (pintype "bidirectional"))
      (node (ref "T2") (pin "15") (pinfunction "TXCT_15") (pintype "bidirectional"))
    )
    (net (code "7") (name "GND") (class "Default")
      (node (ref "C1") (pin "2") (pinfunction "2_2") (pintype "passive"))
      (node (ref "C10") (pin "2") (pinfunction "2_2") (pintype "passive"))
      (node (ref "C11") (pin "2") (pinfunction "2_2") (pintype "passive"))
      (node (ref "C12") (pin "2") (pinfunction "2_2") (pintype "passive"))
      (node (ref "C13") (pin "-") (pinfunction "-_-") (pintype "passive"))
      (node (ref "C14") (pin "-") (pinfunction "-_-") (pintype "passive"))
      (node (ref "C15") (pin "2") (pinfunction "2_2") (pintype "passive"))
      (node (ref "C16") (pin "2") (pinfunction "2_2") (pintype "passive"))
      (node (ref "C17") (pin "2") (pinfunction "2_2") (pintype "passive"))
      (node (ref "C18") (pin "2") (pinfunction "2_2") (pintype "passive"))
      (node (ref "C19") (pin "-") (pinfunction "-_-") (pintype "passive"))
      (node (ref "C2") (pin "2") (pinfunction "2_2") (pintype "passive"))
      (node (ref "C20") (pin "2") (pinfunction "2_2") (pintype "passive"))
      (node (ref "C21") (pin "2") (pinfunction "2_2") (pintype "passive"))
      (node (ref "C22") (pin "2") (pinfunction "2_2") (pintype "passive"))
      (node (ref "C23") (pin "2") (pinfunction "2_2") (pintype "passive"))
      (node (ref "C24") (pin "2") (pinfunction "2_2") (pintype "passive"))
      (node (ref "C25") (pin "2") (pinfunction "2_2") (pintype "passive"))
      (node (ref "C26") (pin "2") (pinfunction "2_2") (pintype "passive"))
      (node (ref "C27") (pin "2") (pinfunction "2_2") (pintype "passive"))
      (node (ref "C28") (pin "2") (pinfunction "2_2") (pintype "passive"))
      (node (ref "C29") (pin "2") (pinfunction "2_2") (pintype "passive"))
      (node (ref "C3") (pin "2") (pinfunction "2_2") (pintype "passive"))
      (node (ref "C30") (pin "2") (pinfunction "2_2") (pintype "passive"))
      (node (ref "C31") (pin "2") (pinfunction "2_2") (pintype "passive"))
      (node (ref "C32") (pin "2") (pinfunction "2_2") (pintype "passive"))
      (node (ref "C33") (pin "2") (pinfunction "2_2") (pintype "passive"))
      (node (ref "C34") (pin "2") (pinfunction "2_2") (pintype "passive"))
      (node (ref "C35") (pin "2") (pinfunction "2_2") (pintype "passive"))
      (node (ref "C36") (pin "2") (pinfunction "2_2") (pintype "passive"))
      (node (ref "C37") (pin "2") (pinfunction "2_2") (pintype "passive"))
      (node (ref "C38") (pin "2") (pinfunction "2_2") (pintype "passive"))
      (node (ref "C39") (pin "2") (pinfunction "2_2") (pintype "passive"))
      (node (ref "C4") (pin "2") (pinfunction "2_2") (pintype "passive"))
      (node (ref "C5") (pin "2") (pinfunction "2_2") (pintype "passive"))
      (node (ref "C6") (pin "2") (pinfunction "2_2") (pintype "passive"))
      (node (ref "C7") (pin "2") (pinfunction "2_2") (pintype "passive"))
      (node (ref "C8") (pin "2") (pinfunction "2_2") (pintype "passive"))
      (node (ref "C9") (pin "2") (pinfunction "2_2") (pintype "passive"))
      (node (ref "D1") (pin "2") (pinfunction "A_2") (pintype "passive"))
      (node (ref "J1") (pin "1") (pinfunction "S_1") (pintype "passive"))
      (node (ref "J4") (pin "20") (pinfunction "P_20") (pintype "bidirectional"))
      (node (ref "J5") (pin "20") (pinfunction "P_20") (pintype "bidirectional"))
      (node (ref "J6") (pin "R4") (pinfunction "R4_R4") (pintype "input"))
      (node (ref "J6") (pin "R5") (pinfunction "R5_R5") (pintype "input"))
      (node (ref "J6") (pin "R6") (pinfunction "R6_R6") (pintype "input"))
      (node (ref "LED1") (pin "C") (pinfunction "C_C") (pintype "passive"))
      (node (ref "R35") (pin "1") (pinfunction "1_1") (pintype "passive"))
      (node (ref "TP5") (pin "TP") (pinfunction "TP_TP") (pintype "input"))
      (node (ref "U1") (pin "2") (pinfunction "GND_2") (pintype "passive"))
      (node (ref "U1") (pin "4") (pinfunction "GND_2_4") (pintype "passive"))
      (node (ref "U2") (pin "2") (pinfunction "GND_2") (pintype "passive"))
      (node (ref "U2") (pin "4") (pinfunction "GND_2_4") (pintype "passive"))
      (node (ref "U3") (pin "116") (pinfunction "GNDD_116") (pintype "power_in"))
      (node (ref "U3") (pin "12") (pinfunction "GNDA_4_12") (pintype "power_in"))
      (node (ref "U3") (pin "124") (pinfunction "GNDA_2_124") (pintype "power_in"))
      (node (ref "U3") (pin "126") (pinfunction "GNDA_3_126") (pintype "power_in"))
      (node (ref "U3") (pin "127") (pinfunction "GNDA_127") (pintype "power_in"))
      (node (ref "U3") (pin "16") (pinfunction "GNDA_5_16") (pintype "power_in"))
      (node (ref "U3") (pin "2") (pinfunction "GNDA_2_2") (pintype "power_in"))
      (node (ref "U3") (pin "21") (pinfunction "GNDA_6_21") (pintype "power_in"))
      (node (ref "U3") (pin "25") (pinfunction "RXP4_25") (pintype "input"))
      (node (ref "U3") (pin "26") (pinfunction "RXM4_26") (pintype "input"))
      (node (ref "U3") (pin "27") (pinfunction "GNDA_7_27") (pintype "power_in"))
      (node (ref "U3") (pin "28") (pinfunction "TXP4_28") (pintype "output"))
      (node (ref "U3") (pin "29") (pinfunction "TXM4_29") (pintype "output"))
      (node (ref "U3") (pin "30") (pinfunction "GNDA_8_30") (pintype "power_in"))
      (node (ref "U3") (pin "32") (pinfunction "RXP5_32") (pintype "input"))
      (node (ref "U3") (pin "33") (pinfunction "RXM5_33") (pintype "input"))
      (node (ref "U3") (pin "34") (pinfunction "GNDA_9_34") (pintype "power_in"))
      (node (ref "U3") (pin "35") (pinfunction "TXP5_35") (pintype "output"))
      (node (ref "U3") (pin "36") (pinfunction "TXM5_36") (pintype "output"))
      (node (ref "U3") (pin "40") (pinfunction "GNDA_10_40") (pintype "power_in"))
      (node (ref "U3") (pin "42") (pinfunction "GNDA_11_42") (pintype "power_in"))
      (node (ref "U3") (pin "44") (pinfunction "GNDA_44") (pintype "power_in"))
      (node (ref "U3") (pin "49") (pinfunction "GNDD_2_49") (pintype "passive"))
      (node (ref "U3") (pin "58") (pinfunction "GNDD_58") (pintype "power_in"))
      (node (ref "U3") (pin "6") (pinfunction "GNDA_3_6") (pintype "power_in"))
      (node (ref "U3") (pin "76") (pinfunction "GNDD_2_76") (pintype "power_in"))
      (node (ref "U3") (pin "88") (pinfunction "GNDD_3_88") (pintype "power_in"))
      (node (ref "U3") (pin "99") (pinfunction "GNDD_4_99") (pintype "power_in"))
      (node (ref "U4") (pin "1") (pinfunction "A0_1") (pintype "input"))
      (node (ref "U4") (pin "2") (pinfunction "A1_2") (pintype "input"))
      (node (ref "U4") (pin "3") (pinfunction "A2_3") (pintype "input"))
      (node (ref "U4") (pin "4") (pinfunction "GND_4") (pintype "power_in"))
      (node (ref "U4") (pin "7") (pinfunction "WP_7") (pintype "input"))
      (node (ref "X1") (pin "2") (pinfunction "2_2") (pintype "passive"))
      (node (ref "X1") (pin "4") (pinfunction "2_4") (pintype "passive"))
    )
    (net (code "8") (name "ISET") (class "Default")
      (node (ref "R35") (pin "2") (pinfunction "2_2") (pintype "passive"))
      (node (ref "U3") (pin "17") (pinfunction "ISET_17") (pintype "output"))
    )
    (net (code "9") (name "L1-1") (class "Default")
      (node (ref "J4") (pin "8") (pinfunction "P_8") (pintype "bidirectional"))
      (node (ref "J5") (pin "8") (pinfunction "P_8") (pintype "bidirectional"))
      (node (ref "LED2") (pin "C") (pinfunction "C_C") (pintype "passive"))
      (node (ref "U3") (pin "102") (pinfunction "LED2-1_102") (pintype "bidirectional"))
    )
    (net (code "10") (name "L1-2") (class "Default")
      (node (ref "J4") (pin "9") (pinfunction "P_9") (pintype "bidirectional"))
      (node (ref "J5") (pin "9") (pinfunction "P_9") (pintype "bidirectional"))
      (node (ref "LED4") (pin "C") (pinfunction "C_C") (pintype "passive"))
      (node (ref "U3") (pin "101") (pinfunction "LED2-2_101") (pintype "bidirectional"))
    )
    (net (code "11") (name "L2-1") (class "Default")
      (node (ref "J4") (pin "18") (pinfunction "P_18") (pintype "bidirectional"))
      (node (ref "J5") (pin "18") (pinfunction "P_18") (pintype "bidirectional"))
      (node (ref "LED3") (pin "C") (pinfunction "C_C") (pintype "passive"))
      (node (ref "U3") (pin "97") (pinfunction "LED3-1_97") (pintype "bidirectional"))
    )
    (net (code "12") (name "L2-2") (class "Default")
      (node (ref "J4") (pin "19") (pinfunction "P_19") (pintype "bidirectional"))
      (node (ref "J5") (pin "19") (pinfunction "P_19") (pintype "bidirectional"))
      (node (ref "LED5") (pin "C") (pinfunction "C_C") (pintype "passive"))
      (node (ref "U3") (pin "96") (pinfunction "LED3-2_96") (pintype "bidirectional"))
    )
    (net (code "13") (name "L3-1") (class "Default")
      (node (ref "J6") (pin "L2") (pinfunction "L2_L2") (pintype "passive"))
      (node (ref "U3") (pin "105") (pinfunction "LED1-1_105") (pintype "bidirectional"))
    )
    (net (code "14") (name "L3-2") (class "Default")
      (node (ref "J6") (pin "L4") (pinfunction "L4_L4") (pintype "passive"))
      (node (ref "U3") (pin "104") (pinfunction "LED1-2_104") (pintype "bidirectional"))
    )
    (net (code "15") (name "Net-(C5-Pad1)") (class "Default")
      (node (ref "C5") (pin "1") (pinfunction "1_1") (pintype "passive"))
      (node (ref "R11") (pin "1") (pinfunction "1_1") (pintype "passive"))
      (node (ref "R14") (pin "1") (pinfunction "1_1") (pintype "passive"))
      (node (ref "R5") (pin "1") (pinfunction "1_1") (pintype "passive"))
    )
    (net (code "16") (name "Net-(C6-Pad1)") (class "Default")
      (node (ref "C6") (pin "1") (pinfunction "1_1") (pintype "passive"))
      (node (ref "R13") (pin "1") (pinfunction "1_1") (pintype "passive"))
      (node (ref "R15") (pin "1") (pinfunction "1_1") (pintype "passive"))
      (node (ref "R7") (pin "1") (pinfunction "1_1") (pintype "passive"))
    )
    (net (code "17") (name "Net-(C15-Pad1)") (class "Default")
      (node (ref "C15") (pin "1") (pinfunction "1_1") (pintype "passive"))
      (node (ref "R20") (pin "1") (pinfunction "1_1") (pintype "passive"))
      (node (ref "R22") (pin "1") (pinfunction "1_1") (pintype "passive"))
    )
    (net (code "18") (name "Net-(C16-Pad1)") (class "Default")
      (node (ref "C16") (pin "1") (pinfunction "1_1") (pintype "passive"))
      (node (ref "R21") (pin "1") (pinfunction "1_1") (pintype "passive"))
      (node (ref "R23") (pin "1") (pinfunction "1_1") (pintype "passive"))
    )
    (net (code "19") (name "Net-(C17-Pad1)") (class "Default")
      (node (ref "C17") (pin "1") (pinfunction "1_1") (pintype "passive"))
      (node (ref "R24") (pin "1") (pinfunction "1_1") (pintype "passive"))
      (node (ref "R26") (pin "1") (pinfunction "1_1") (pintype "passive"))
    )
    (net (code "20") (name "Net-(C18-Pad1)") (class "Default")
      (node (ref "C18") (pin "1") (pinfunction "1_1") (pintype "passive"))
      (node (ref "R25") (pin "1") (pinfunction "1_1") (pintype "passive"))
      (node (ref "R27") (pin "1") (pinfunction "1_1") (pintype "passive"))
    )
    (net (code "21") (name "Net-(C20-Pad1)") (class "Default")
      (node (ref "C20") (pin "1") (pinfunction "1_1") (pintype "passive"))
      (node (ref "R30") (pin "1") (pinfunction "1_1") (pintype "passive"))
      (node (ref "R31") (pin "1") (pinfunction "1_1") (pintype "passive"))
    )
    (net (code "22") (name "Net-(C21-Pad1)") (class "Default")
      (node (ref "C21") (pin "1") (pinfunction "1_1") (pintype "passive"))
      (node (ref "R32") (pin "1") (pinfunction "1_1") (pintype "passive"))
      (node (ref "R33") (pin "1") (pinfunction "1_1") (pintype "passive"))
    )
    (net (code "23") (name "Net-(D1-C)") (class "Default")
      (node (ref "C3") (pin "1") (pinfunction "1_1") (pintype "passive"))
      (node (ref "C4") (pin "1") (pinfunction "1_1") (pintype "passive"))
      (node (ref "D1") (pin "1") (pinfunction "C_1") (pintype "passive"))
      (node (ref "F1") (pin "2") (pinfunction "2_2") (pintype "passive"))
      (node (ref "L1") (pin "1") (pinfunction "1_1") (pintype "passive"))
    )
    (net (code "24") (name "Net-(J1B-S)") (class "Default")
      (node (ref "F1") (pin "1") (pinfunction "1_1") (pintype "passive"))
      (node (ref "J1") (pin "2") (pinfunction "S_2") (pintype "passive"))
    )
    (net (code "25") (name "Net-(J2-Pad4)") (class "Default")
      (node (ref "J2") (pin "4") (pinfunction "4_4") (pintype "passive"))
      (node (ref "R1") (pin "2") (pinfunction "2_2") (pintype "passive"))
    )
    (net (code "26") (name "Net-(J2-Pad5)") (class "Default")
      (node (ref "J2") (pin "5") (pinfunction "5_5") (pintype "passive"))
      (node (ref "R12") (pin "2") (pinfunction "2_2") (pintype "passive"))
    )
    (net (code "27") (name "Net-(J2-Pad7)") (class "Default")
      (node (ref "J2") (pin "7") (pinfunction "7_7") (pintype "passive"))
      (node (ref "R9") (pin "2") (pinfunction "2_2") (pintype "passive"))
    )
    (net (code "28") (name "Net-(J2-Pad8)") (class "Default")
      (node (ref "J2") (pin "8") (pinfunction "8_8") (pintype "passive"))
      (node (ref "R6") (pin "2") (pinfunction "2_2") (pintype "passive"))
    )
    (net (code "29") (name "Net-(J3-Pad4)") (class "Default")
      (node (ref "J3") (pin "4") (pinfunction "4_4") (pintype "passive"))
      (node (ref "R2") (pin "2") (pinfunction "2_2") (pintype "passive"))
    )
    (net (code "30") (name "Net-(J3-Pad5)") (class "Default")
      (node (ref "J3") (pin "5") (pinfunction "5_5") (pintype "passive"))
      (node (ref "R10") (pin "2") (pinfunction "2_2") (pintype "passive"))
    )
    (net (code "31") (name "Net-(J3-Pad7)") (class "Default")
      (node (ref "J3") (pin "7") (pinfunction "7_7") (pintype "passive"))
      (node (ref "R8") (pin "2") (pinfunction "2_2") (pintype "passive"))
    )
    (net (code "32") (name "Net-(J3-Pad8)") (class "Default")
      (node (ref "J3") (pin "8") (pinfunction "8_8") (pintype "passive"))
      (node (ref "R4") (pin "2") (pinfunction "2_2") (pintype "passive"))
    )
    (net (code "33") (name "Net-(J6-PadL1)") (class "Default")
      (node (ref "J6") (pin "L1") (pinfunction "L1_L1") (pintype "passive"))
      (node (ref "R28") (pin "2") (pinfunction "2_2") (pintype "passive"))
    )
    (net (code "34") (name "Net-(J6-PadL3)") (class "Default")
      (node (ref "J6") (pin "L3") (pinfunction "L3_L3") (pintype "passive"))
      (node (ref "R29") (pin "2") (pinfunction "2_2") (pintype "passive"))
    )
    (net (code "35") (name "Net-(LED1-PadA)") (class "Default")
      (node (ref "LED1") (pin "A") (pinfunction "A_A") (pintype "passive"))
      (node (ref "R3") (pin "1") (pinfunction "1_1") (pintype "passive"))
    )
    (net (code "36") (name "Net-(LED2-PadA)") (class "Default")
      (node (ref "LED2") (pin "A") (pinfunction "A_A") (pintype "passive"))
      (node (ref "R16") (pin "1") (pinfunction "1_1") (pintype "passive"))
    )
    (net (code "37") (name "Net-(LED3-PadA)") (class "Default")
      (node (ref "LED3") (pin "A") (pinfunction "A_A") (pintype "passive"))
      (node (ref "R17") (pin "1") (pinfunction "1_1") (pintype "passive"))
    )
    (net (code "38") (name "Net-(LED4-PadA)") (class "Default")
      (node (ref "LED4") (pin "A") (pinfunction "A_A") (pintype "passive"))
      (node (ref "R18") (pin "1") (pinfunction "1_1") (pintype "passive"))
    )
    (net (code "39") (name "Net-(LED5-PadA)") (class "Default")
      (node (ref "LED5") (pin "A") (pinfunction "A_A") (pintype "passive"))
      (node (ref "R19") (pin "1") (pinfunction "1_1") (pintype "passive"))
    )
    (net (code "40") (name "Net-(R1-Pad1)") (class "Default")
      (node (ref "R1") (pin "1") (pinfunction "1_1") (pintype "passive"))
      (node (ref "R6") (pin "1") (pinfunction "1_1") (pintype "passive"))
      (node (ref "R7") (pin "2") (pinfunction "2_2") (pintype "passive"))
    )
    (net (code "41") (name "Net-(R2-Pad1)") (class "Default")
      (node (ref "R2") (pin "1") (pinfunction "1_1") (pintype "passive"))
      (node (ref "R4") (pin "1") (pinfunction "1_1") (pintype "passive"))
      (node (ref "R5") (pin "2") (pinfunction "2_2") (pintype "passive"))
    )
    (net (code "42") (name "Net-(R10-Pad1)") (class "Default")
      (node (ref "R10") (pin "1") (pinfunction "1_1") (pintype "passive"))
      (node (ref "R11") (pin "2") (pinfunction "2_2") (pintype "passive"))
      (node (ref "R8") (pin "1") (pinfunction "1_1") (pintype "passive"))
    )
    (net (code "43") (name "Net-(R12-Pad1)") (class "Default")
      (node (ref "R12") (pin "1") (pinfunction "1_1") (pintype "passive"))
      (node (ref "R13") (pin "2") (pinfunction "2_2") (pintype "passive"))
      (node (ref "R9") (pin "1") (pinfunction "1_1") (pintype "passive"))
    )
    (net (code "44") (name "PS0") (class "Default")
      (node (ref "R37") (pin "1") (pinfunction "1_1") (pintype "passive"))
      (node (ref "U3") (pin "114") (pinfunction "PS0_114") (pintype "input"))
    )
    (net (code "45") (name "PS1") (class "Default")
      (node (ref "R36") (pin "1") (pinfunction "1_1") (pintype "passive"))
      (node (ref "U3") (pin "113") (pinfunction "PS1_113") (pintype "input"))
    )
    (net (code "46") (name "PWRDN_N") (class "Default")
      (node (ref "U3") (pin "47") (pinfunction "PWRDN_N_47") (pintype "input"))
    )
    (net (code "47") (name "RST_N") (class "Default")
      (node (ref "C23") (pin "1") (pinfunction "1_1") (pintype "passive"))
      (node (ref "D2") (pin "A") (pinfunction "2_A") (pintype "passive"))
      (node (ref "R34") (pin "1") (pinfunction "1_1") (pintype "passive"))
      (node (ref "U3") (pin "115") (pinfunction "RST_N_115") (pintype "input"))
    )
    (net (code "48") (name "RX1_ISO_N") (class "Default")
      (node (ref "R24") (pin "2") (pinfunction "2_2") (pintype "passive"))
      (node (ref "T1") (pin "8") (pinfunction "RD-_8") (pintype "bidirectional"))
      (node (ref "U3") (pin "11") (pinfunction "RXM2_11") (pintype "input"))
    )
    (net (code "49") (name "RX1_ISO_P") (class "Default")
      (node (ref "R26") (pin "2") (pinfunction "2_2") (pintype "passive"))
      (node (ref "T1") (pin "6") (pinfunction "RD+_6") (pintype "bidirectional"))
      (node (ref "U3") (pin "10") (pinfunction "RXP2_10") (pintype "input"))
    )
    (net (code "50") (name "RX1_N") (class "Default")
      (node (ref "J2") (pin "2") (pinfunction "2_2") (pintype "passive"))
      (node (ref "J4") (pin "3") (pinfunction "P_3") (pintype "bidirectional"))
      (node (ref "J5") (pin "3") (pinfunction "P_3") (pintype "bidirectional"))
      (node (ref "T1") (pin "9") (pinfunction "RX-_9") (pintype "bidirectional"))
    )
    (net (code "51") (name "RX1_P") (class "Default")
      (node (ref "J2") (pin "1") (pinfunction "1_1") (pintype "passive"))
      (node (ref "J4") (pin "2") (pinfunction "P_2") (pintype "bidirectional"))
      (node (ref "J5") (pin "2") (pinfunction "P_2") (pintype "bidirectional"))
      (node (ref "T1") (pin "11") (pinfunction "RX+_11") (pintype "bidirectional"))
    )
    (net (code "52") (name "RX2_ISO_N") (class "Default")
      (node (ref "R25") (pin "2") (pinfunction "2_2") (pintype "passive"))
      (node (ref "T2") (pin "8") (pinfunction "RD-_8") (pintype "bidirectional"))
      (node (ref "U3") (pin "20") (pinfunction "RXM3_20") (pintype "input"))
    )
    (net (code "53") (name "RX2_ISO_P") (class "Default")
      (node (ref "R27") (pin "2") (pinfunction "2_2") (pintype "passive"))
      (node (ref "T2") (pin "6") (pinfunction "RD+_6") (pintype "bidirectional"))
      (node (ref "U3") (pin "19") (pinfunction "RXP3_19") (pintype "input"))
    )
    (net (code "54") (name "RX2_N") (class "Default")
      (node (ref "J3") (pin "2") (pinfunction "2_2") (pintype "passive"))
      (node (ref "J4") (pin "13") (pinfunction "P_13") (pintype "bidirectional"))
      (node (ref "J5") (pin "13") (pinfunction "P_13") (pintype "bidirectional"))
      (node (ref "T2") (pin "9") (pinfunction "RX-_9") (pintype "bidirectional"))
    )
    (net (code "55") (name "RX2_P") (class "Default")
      (node (ref "J3") (pin "1") (pinfunction "1_1") (pintype "passive"))
      (node (ref "J4") (pin "12") (pinfunction "P_12") (pintype "bidirectional"))
      (node (ref "J5") (pin "12") (pinfunction "P_12") (pintype "bidirectional"))
      (node (ref "T2") (pin "11") (pinfunction "RX+_11") (pintype "bidirectional"))
    )
    (net (code "56") (name "RX3_ISO_N") (class "Default")
      (node (ref "J6") (pin "R8") (pinfunction "RD-_R8") (pintype "input"))
      (node (ref "R33") (pin "2") (pinfunction "2_2") (pintype "passive"))
      (node (ref "U3") (pin "5") (pinfunction "RXM1_5") (pintype "input"))
    )
    (net (code "57") (name "RX3_ISO_P") (class "Default")
      (node (ref "J6") (pin "R7") (pinfunction "RD+_R7") (pintype "input"))
      (node (ref "R32") (pin "2") (pinfunction "2_2") (pintype "passive"))
      (node (ref "U3") (pin "4") (pinfunction "RXP1_4") (pintype "input"))
    )
    (net (code "58") (name "SCL") (class "Default")
      (node (ref "R40") (pin "1") (pinfunction "1_1") (pintype "passive"))
      (node (ref "R41") (pin "1") (pinfunction "1_1") (pintype "passive"))
      (node (ref "U3") (pin "110") (pinfunction "SPIC/SCL_110") (pintype "bidirectional"))
    )
    (net (code "59") (name "SCL_CPU") (class "Default")
      (node (ref "R41") (pin "2") (pinfunction "2_2") (pintype "passive"))
      (node (ref "TP2") (pin "TP") (pinfunction "TP_TP") (pintype "input"))
    )
    (net (code "60") (name "SCL_EEPROM") (class "Default")
      (node (ref "R40") (pin "2") (pinfunction "2_2") (pintype "passive"))
      (node (ref "U4") (pin "6") (pinfunction "SCL_6") (pintype "input"))
    )
    (net (code "61") (name "SDA") (class "Default")
      (node (ref "R38") (pin "1") (pinfunction "1_1") (pintype "passive"))
      (node (ref "R39") (pin "1") (pinfunction "1_1") (pintype "passive"))
      (node (ref "U3") (pin "111") (pinfunction "SSPID/SDA_111") (pintype "bidirectional"))
    )
    (net (code "62") (name "SDA_CPU") (class "Default")
      (node (ref "R39") (pin "2") (pinfunction "2_2") (pintype "passive"))
      (node (ref "TP3") (pin "TP") (pinfunction "TP_TP") (pintype "input"))
    )
    (net (code "63") (name "SDA_EEPROM") (class "Default")
      (node (ref "R38") (pin "2") (pinfunction "2_2") (pintype "passive"))
      (node (ref "U4") (pin "5") (pinfunction "SDA_5") (pintype "bidirectional"))
    )
    (net (code "64") (name "SPIQ") (class "Default")
      (node (ref "R42") (pin "1") (pinfunction "1_1") (pintype "passive"))
      (node (ref "U3") (pin "109") (pinfunction "SPIQ_109") (pintype "output"))
    )
    (net (code "65") (name "SPIQ_CPU") (class "Default")
      (node (ref "R42") (pin "2") (pinfunction "2_2") (pintype "passive"))
      (node (ref "TP1") (pin "TP") (pinfunction "TP_TP") (pintype "input"))
    )
    (net (code "66") (name "SPIS-N") (class "Default")
      (node (ref "R43") (pin "1") (pinfunction "1_1") (pintype "passive"))
      (node (ref "U3") (pin "112") (pinfunction "SPIS_N_112") (pintype "input"))
    )
    (net (code "67") (name "SPIS-N_CPU") (class "Default")
      (node (ref "R43") (pin "2") (pinfunction "2_2") (pintype "passive"))
      (node (ref "TP4") (pin "TP") (pinfunction "TP_TP") (pintype "input"))
    )
    (net (code "68") (name "TX1_ISO_N") (class "Default")
      (node (ref "R20") (pin "2") (pinfunction "2_2") (pintype "passive"))
      (node (ref "T1") (pin "3") (pinfunction "TD-_3") (pintype "bidirectional"))
      (node (ref "U3") (pin "14") (pinfunction "TXM2_14") (pintype "output"))
    )
    (net (code "69") (name "TX1_ISO_P") (class "Default")
      (node (ref "R22") (pin "2") (pinfunction "2_2") (pintype "passive"))
      (node (ref "T1") (pin "1") (pinfunction "TD+_1") (pintype "bidirectional"))
      (node (ref "U3") (pin "13") (pinfunction "TXP2_13") (pintype "output"))
    )
    (net (code "70") (name "TX1_N") (class "Default")
      (node (ref "J2") (pin "6") (pinfunction "6_6") (pintype "passive"))
      (node (ref "J4") (pin "6") (pinfunction "P_6") (pintype "bidirectional"))
      (node (ref "J5") (pin "6") (pinfunction "P_6") (pintype "bidirectional"))
      (node (ref "T1") (pin "14") (pinfunction "TX-_14") (pintype "bidirectional"))
    )
    (net (code "71") (name "TX1_P") (class "Default")
      (node (ref "J2") (pin "3") (pinfunction "3_3") (pintype "passive"))
      (node (ref "J4") (pin "5") (pinfunction "P_5") (pintype "bidirectional"))
      (node (ref "J5") (pin "5") (pinfunction "P_5") (pintype "bidirectional"))
      (node (ref "T1") (pin "16") (pinfunction "TX+_16") (pintype "bidirectional"))
    )
    (net (code "72") (name "TX2_ISO_N") (class "Default")
      (node (ref "R21") (pin "2") (pinfunction "2_2") (pintype "passive"))
      (node (ref "T2") (pin "3") (pinfunction "TD-_3") (pintype "bidirectional"))
      (node (ref "U3") (pin "23") (pinfunction "TXM3_23") (pintype "output"))
    )
    (net (code "73") (name "TX2_ISO_P") (class "Default")
      (node (ref "R23") (pin "2") (pinfunction "2_2") (pintype "passive"))
      (node (ref "T2") (pin "1") (pinfunction "TD+_1") (pintype "bidirectional"))
      (node (ref "U3") (pin "22") (pinfunction "TXP3_22") (pintype "output"))
    )
    (net (code "74") (name "TX2_N") (class "Default")
      (node (ref "J3") (pin "6") (pinfunction "6_6") (pintype "passive"))
      (node (ref "J4") (pin "16") (pinfunction "P_16") (pintype "bidirectional"))
      (node (ref "J5") (pin "16") (pinfunction "P_16") (pintype "bidirectional"))
      (node (ref "T2") (pin "14") (pinfunction "TX-_14") (pintype "bidirectional"))
    )
    (net (code "75") (name "TX2_P") (class "Default")
      (node (ref "J3") (pin "3") (pinfunction "3_3") (pintype "passive"))
      (node (ref "J4") (pin "15") (pinfunction "P_15") (pintype "bidirectional"))
      (node (ref "J5") (pin "15") (pinfunction "P_15") (pintype "bidirectional"))
      (node (ref "T2") (pin "16") (pinfunction "TX+_16") (pintype "bidirectional"))
    )
    (net (code "76") (name "TX3_ISO_N") (class "Default")
      (node (ref "J6") (pin "R2") (pinfunction "TD-_R2") (pintype "input"))
      (node (ref "R31") (pin "2") (pinfunction "2_2") (pintype "passive"))
      (node (ref "U3") (pin "8") (pinfunction "TXM1_8") (pintype "output"))
    )
    (net (code "77") (name "TX3_ISO_P") (class "Default")
      (node (ref "J6") (pin "R1") (pinfunction "TD+_R1") (pintype "input"))
      (node (ref "R30") (pin "2") (pinfunction "2_2") (pintype "passive"))
      (node (ref "U3") (pin "7") (pinfunction "TXP1_7") (pintype "output"))
    )
    (net (code "78") (name "X1") (class "Default")
      (node (ref "C22") (pin "1") (pinfunction "1_1") (pintype "passive"))
      (node (ref "U3") (pin "121") (pinfunction "X1_121") (pintype "input"))
      (node (ref "X1") (pin "1") (pinfunction "1_1") (pintype "passive"))
    )
    (net (code "79") (name "X2") (class "Default")
      (node (ref "C24") (pin "1") (pinfunction "1_1") (pintype "passive"))
      (node (ref "U3") (pin "122") (pinfunction "X2_122") (pintype "output"))
      (node (ref "X1") (pin "3") (pinfunction "3_3") (pintype "passive"))
    )
    (net (code "80") (name "unconnected-(J4F-P-Pad14)") (class "Default")
      (node (ref "J4") (pin "14") (pinfunction "P_14") (pintype "bidirectional"))
    )
    (net (code "81") (name "unconnected-(J4I-P-Pad17)") (class "Default")
      (node (ref "J4") (pin "17") (pinfunction "P_17") (pintype "bidirectional"))
    )
    (net (code "82") (name "unconnected-(J4O-P-Pad4)") (class "Default")
      (node (ref "J4") (pin "4") (pinfunction "P_4") (pintype "bidirectional"))
    )
    (net (code "83") (name "unconnected-(J4R-P-Pad7)") (class "Default")
      (node (ref "J4") (pin "7") (pinfunction "P_7") (pintype "bidirectional"))
    )
    (net (code "84") (name "unconnected-(J5F-P-Pad14)") (class "Default")
      (node (ref "J5") (pin "14") (pinfunction "P_14") (pintype "bidirectional"))
    )
    (net (code "85") (name "unconnected-(J5I-P-Pad17)") (class "Default")
      (node (ref "J5") (pin "17") (pinfunction "P_17") (pintype "bidirectional"))
    )
    (net (code "86") (name "unconnected-(J5O-P-Pad4)") (class "Default")
      (node (ref "J5") (pin "4") (pinfunction "P_4") (pintype "bidirectional"))
    )
    (net (code "87") (name "unconnected-(J5R-P-Pad7)") (class "Default")
      (node (ref "J5") (pin "7") (pinfunction "P_7") (pintype "bidirectional"))
    )
    (net (code "88") (name "unconnected-(U3A-FXSD4-Pad39)") (class "Default")
      (node (ref "U3") (pin "39") (pinfunction "FXSD4_39") (pintype "input"))
    )
    (net (code "89") (name "unconnected-(U3A-FXSD5{slash}FXSD3-Pad38)") (class "Default")
      (node (ref "U3") (pin "38") (pinfunction "FXSD5/FXSD3_38") (pintype "input"))
    )
    (net (code "90") (name "unconnected-(U3A-MDI-XDIS-Pad1)") (class "Default")
      (node (ref "U3") (pin "1") (pinfunction "MDI-XDIS_1") (pintype "input"))
    )
    (net (code "91") (name "unconnected-(U3A-MUX1-Pad45)") (class "Default")
      (node (ref "U3") (pin "45") (pinfunction "MUX1_45") (pintype "passive"))
    )
    (net (code "92") (name "unconnected-(U3A-MUX2-Pad46)") (class "Default")
      (node (ref "U3") (pin "46") (pinfunction "MUX2_46") (pintype "passive"))
    )
    (net (code "93") (name "unconnected-(U3A-PMRXC-Pad60)") (class "Default")
      (node (ref "U3") (pin "60") (pinfunction "PMRXC_60") (pintype "output"))
    )
    (net (code "94") (name "unconnected-(U3A-PMRXD1-Pad64)") (class "Default")
      (node (ref "U3") (pin "64") (pinfunction "PMRXD1_64") (pintype "bidirectional"))
    )
    (net (code "95") (name "unconnected-(U3A-PMRXD2-Pad63)") (class "Default")
      (node (ref "U3") (pin "63") (pinfunction "PMRXD2_63") (pintype "bidirectional"))
    )
    (net (code "96") (name "unconnected-(U3A-PMRXD3-Pad62)") (class "Default")
      (node (ref "U3") (pin "62") (pinfunction "PMRXD3_62") (pintype "bidirectional"))
    )
    (net (code "97") (name "unconnected-(U3A-PMRXDV-Pad61)") (class "Default")
      (node (ref "U3") (pin "61") (pinfunction "PMRXDV_61") (pintype "bidirectional"))
    )
    (net (code "98") (name "unconnected-(U3A-PMTXC-Pad57)") (class "Default")
      (node (ref "U3") (pin "57") (pinfunction "PMTXC_57") (pintype "output"))
    )
    (net (code "99") (name "unconnected-(U3A-PMTXD0-Pad55)") (class "Default")
      (node (ref "U3") (pin "55") (pinfunction "PMTXD0_55") (pintype "input"))
    )
    (net (code "100") (name "unconnected-(U3A-PMTXD1-Pad54)") (class "Default")
      (node (ref "U3") (pin "54") (pinfunction "PMTXD1_54") (pintype "input"))
    )
    (net (code "101") (name "unconnected-(U3A-PMTXD2-Pad53)") (class "Default")
      (node (ref "U3") (pin "53") (pinfunction "PMTXD2_53") (pintype "input"))
    )
    (net (code "102") (name "unconnected-(U3A-PMTXD3-Pad52)") (class "Default")
      (node (ref "U3") (pin "52") (pinfunction "PMTXD3_52") (pintype "input"))
    )
    (net (code "103") (name "unconnected-(U3A-PMTXEN-Pad51)") (class "Default")
      (node (ref "U3") (pin "51") (pinfunction "PMTXEN_51") (pintype "input"))
    )
    (net (code "104") (name "unconnected-(U3A-PMTXER-Pad56)") (class "Default")
      (node (ref "U3") (pin "56") (pinfunction "PMTXER_56") (pintype "input"))
    )
    (net (code "105") (name "unconnected-(U3A-RESERVE-Pad48)") (class "Default")
      (node (ref "U3") (pin "48") (pinfunction "RESERVE_48") (pintype "passive"))
    )
    (net (code "106") (name "unconnected-(U3B-LED1-0-Pad106)") (class "Default")
      (node (ref "U3") (pin "106") (pinfunction "LED1-0_106") (pintype "bidirectional"))
    )
    (net (code "107") (name "unconnected-(U3B-LED2-0-Pad103)") (class "Default")
      (node (ref "U3") (pin "103") (pinfunction "LED2-0_103") (pintype "bidirectional"))
    )
    (net (code "108") (name "unconnected-(U3B-LED3-0-Pad98)") (class "Default")
      (node (ref "U3") (pin "98") (pinfunction "LED3-0_98") (pintype "bidirectional"))
    )
    (net (code "109") (name "unconnected-(U3B-LED4-0-Pad95)") (class "Default")
      (node (ref "U3") (pin "95") (pinfunction "LED4-0_95") (pintype "bidirectional"))
    )
    (net (code "110") (name "unconnected-(U3B-LED4-1-Pad94)") (class "Default")
      (node (ref "U3") (pin "94") (pinfunction "LED4-1_94") (pintype "bidirectional"))
    )
    (net (code "111") (name "unconnected-(U3B-LED4-2-Pad93)") (class "Default")
      (node (ref "U3") (pin "93") (pinfunction "LED4-2_93") (pintype "bidirectional"))
    )
    (net (code "112") (name "unconnected-(U3B-LED5-0-Pad92)") (class "Default")
      (node (ref "U3") (pin "92") (pinfunction "LED5-0_92") (pintype "bidirectional"))
    )
    (net (code "113") (name "unconnected-(U3B-LED5-1-Pad91)") (class "Default")
      (node (ref "U3") (pin "91") (pinfunction "LED5-1_91") (pintype "bidirectional"))
    )
    (net (code "114") (name "unconnected-(U3B-LED5-2-Pad90)") (class "Default")
      (node (ref "U3") (pin "90") (pinfunction "LED5-2_90") (pintype "bidirectional"))
    )
    (net (code "115") (name "unconnected-(U3B-MDC-Pad107)") (class "Default")
      (node (ref "U3") (pin "107") (pinfunction "MDC_107") (pintype "input"))
    )
    (net (code "116") (name "unconnected-(U3B-MDIO-Pad108)") (class "Default")
      (node (ref "U3") (pin "108") (pinfunction "MDIO_108") (pintype "bidirectional"))
    )
    (net (code "117") (name "unconnected-(U3B-NC-Pad120)") (class "Default")
      (node (ref "U3") (pin "120") (pinfunction "NC_120") (pintype "no_connect"))
    )
    (net (code "118") (name "unconnected-(U3B-PCOL-Pad68)") (class "Default")
      (node (ref "U3") (pin "68") (pinfunction "PCOL_68") (pintype "bidirectional"))
    )
    (net (code "119") (name "unconnected-(U3B-PCRS-Pad67)") (class "Default")
      (node (ref "U3") (pin "67") (pinfunction "PCRS_67") (pintype "bidirectional"))
    )
    (net (code "120") (name "unconnected-(U3B-PMRXD0-Pad65)") (class "Default")
      (node (ref "U3") (pin "65") (pinfunction "PMRXD0_65") (pintype "bidirectional"))
    )
    (net (code "121") (name "unconnected-(U3B-PMRXER-Pad66)") (class "Default")
      (node (ref "U3") (pin "66") (pinfunction "PMRXER_66") (pintype "bidirectional"))
    )
    (net (code "122") (name "unconnected-(U3B-SCANEN-Pad119)") (class "Default")
      (node (ref "U3") (pin "119") (pinfunction "SCANEN_119") (pintype "input"))
    )
    (net (code "123") (name "unconnected-(U3B-SCOL-Pad84)") (class "Default")
      (node (ref "U3") (pin "84") (pinfunction "SCOL_84") (pintype "bidirectional"))
    )
    (net (code "124") (name "unconnected-(U3B-SCONF0-Pad87)") (class "Default")
      (node (ref "U3") (pin "87") (pinfunction "SCONF0_87") (pintype "input"))
    )
    (net (code "125") (name "unconnected-(U3B-SCONF1-Pad86)") (class "Default")
      (node (ref "U3") (pin "86") (pinfunction "SCONF1_86") (pintype "input"))
    )
    (net (code "126") (name "unconnected-(U3B-SCRS-Pad85)") (class "Default")
      (node (ref "U3") (pin "85") (pinfunction "SCRS_85") (pintype "bidirectional"))
    )
    (net (code "127") (name "unconnected-(U3B-SMRXC-Pad78)") (class "Default")
      (node (ref "U3") (pin "78") (pinfunction "SMRXC_78") (pintype "bidirectional"))
    )
    (net (code "128") (name "unconnected-(U3B-SMRXD0-Pad83)") (class "Default")
      (node (ref "U3") (pin "83") (pinfunction "SMRXD0_83") (pintype "bidirectional"))
    )
    (net (code "129") (name "unconnected-(U3B-SMRXD1-Pad82)") (class "Default")
      (node (ref "U3") (pin "82") (pinfunction "SMRXD1_82") (pintype "bidirectional"))
    )
    (net (code "130") (name "unconnected-(U3B-SMRXD2-Pad81)") (class "Default")
      (node (ref "U3") (pin "81") (pinfunction "SMRXD2_81") (pintype "bidirectional"))
    )
    (net (code "131") (name "unconnected-(U3B-SMRXD3-Pad80)") (class "Default")
      (node (ref "U3") (pin "80") (pinfunction "SMRXD3_80") (pintype "bidirectional"))
    )
    (net (code "132") (name "unconnected-(U3B-SMRXDV-Pad79)") (class "Default")
      (node (ref "U3") (pin "79") (pinfunction "SMRXDV_79") (pintype "bidirectional"))
    )
    (net (code "133") (name "unconnected-(U3B-SMTXC-Pad75)") (class "Default")
      (node (ref "U3") (pin "75") (pinfunction "SMTXC_75") (pintype "bidirectional"))
    )
    (net (code "134") (name "unconnected-(U3B-SMTXD0-Pad73)") (class "Default")
      (node (ref "U3") (pin "73") (pinfunction "SMTXD0_73") (pintype "input"))
    )
    (net (code "135") (name "unconnected-(U3B-SMTXD1-Pad72)") (class "Default")
      (node (ref "U3") (pin "72") (pinfunction "SMTXD1_72") (pintype "input"))
    )
    (net (code "136") (name "unconnected-(U3B-SMTXD2-Pad71)") (class "Default")
      (node (ref "U3") (pin "71") (pinfunction "SMTXD2_71") (pintype "input"))
    )
    (net (code "137") (name "unconnected-(U3B-SMTXD3-Pad70)") (class "Default")
      (node (ref "U3") (pin "70") (pinfunction "SMTXD3_70") (pintype "input"))
    )
    (net (code "138") (name "unconnected-(U3B-SMTXEN-Pad69)") (class "Default")
      (node (ref "U3") (pin "69") (pinfunction "SMTXEN_69") (pintype "input"))
    )
    (net (code "139") (name "unconnected-(U3B-SMTXER-Pad74)") (class "Default")
      (node (ref "U3") (pin "74") (pinfunction "SMTXER_74") (pintype "input"))
    )
    (net (code "140") (name "unconnected-(U3B-TEST2-Pad128)") (class "Default")
      (node (ref "U3") (pin "128") (pinfunction "TEST2_128") (pintype "passive"))
    )
    (net (code "141") (name "unconnected-(U3B-TESTEN-Pad118)") (class "Default")
      (node (ref "U3") (pin "118") (pinfunction "TESTEN_118") (pintype "input"))
    )
  )
)
